# SODIMM_Connector.net
KiCad netlist of a schematic drawn in Altium Designer
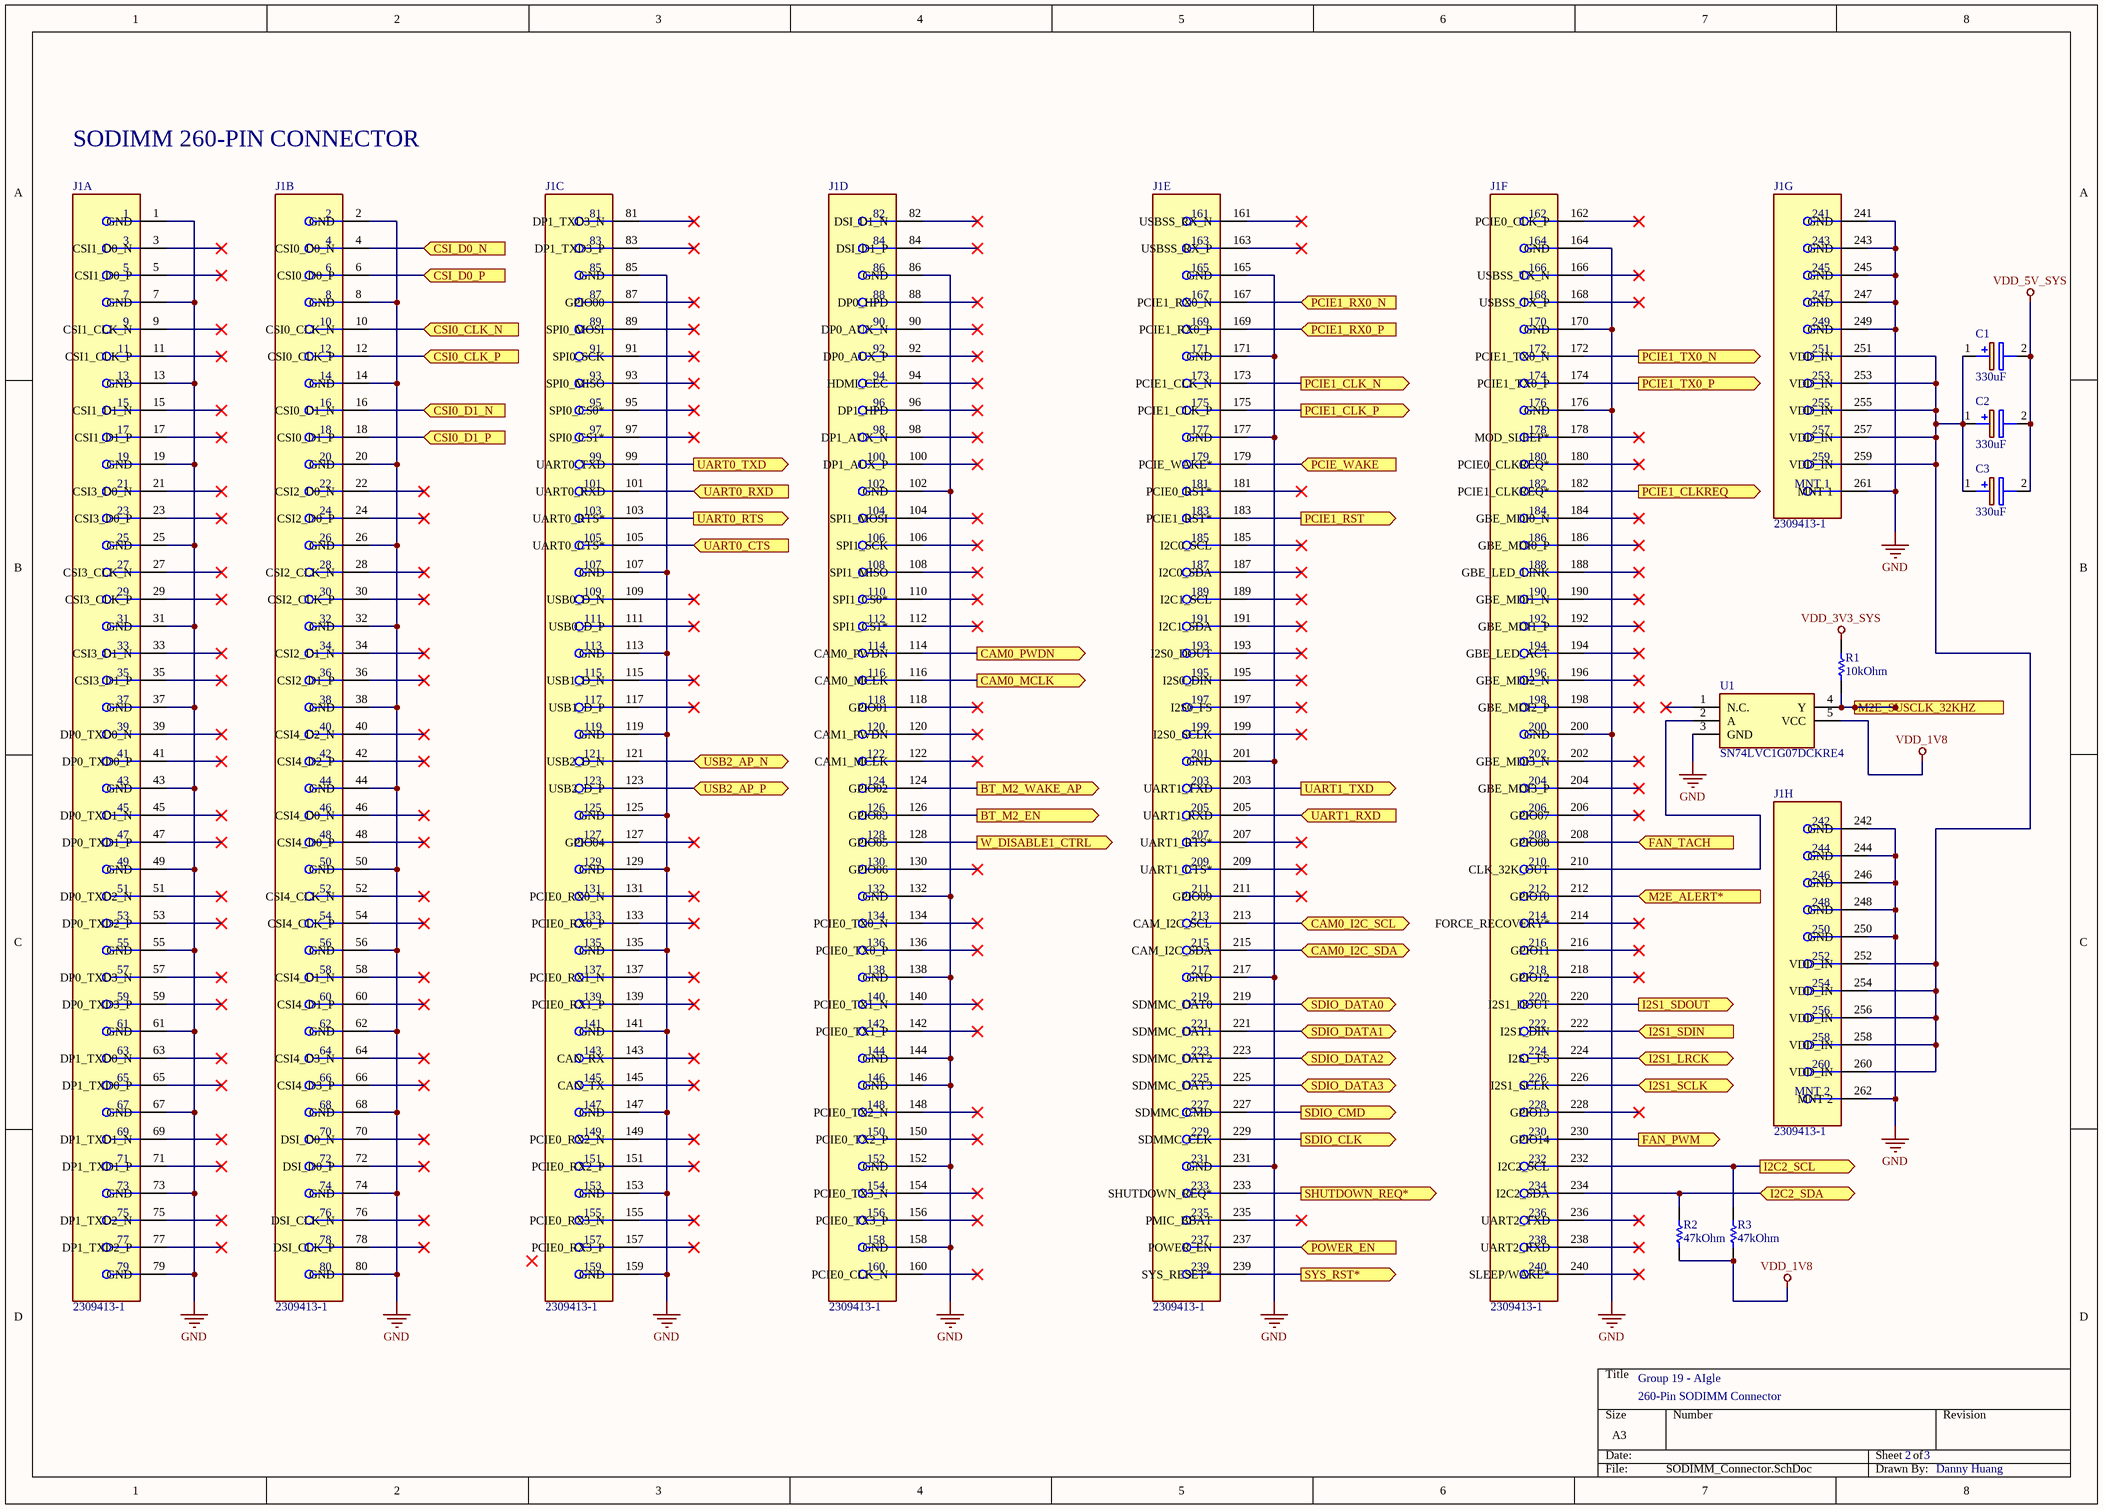
[diagram p0: SODIMM_Connector.SchDoc]

(export (version "E")
  (design (tool "Eeschema 10.0.6"))
  (components
    (comp (ref "C1")
      (value "330uF")
      (footprint "SamacSys:CAPPM3528X210N")
      (description "Capacitor Polarised")
      (fields
        (field (name "MANUFACTURER_PART_NUMBER") "T520B337M006ATE040")
        (field (name "MOUSER PART NUMBER") "80-T520B337M06ATE040")
      )
      (libsource (lib "*") (part "T520B337M006ATE040"))
    )
    (comp (ref "C2")
      (value "330uF")
      (footprint "SamacSys:CAPPM3528X210N")
      (description "Capacitor Polarised")
      (fields
        (field (name "MANUFACTURER_PART_NUMBER") "T520B337M006ATE040")
        (field (name "MOUSER PART NUMBER") "80-T520B337M06ATE040")
      )
      (libsource (lib "*") (part "T520B337M006ATE040"))
    )
    (comp (ref "C3")
      (value "330uF")
      (footprint "SamacSys:CAPPM3528X210N")
      (description "Capacitor Polarised")
      (fields
        (field (name "MANUFACTURER_PART_NUMBER") "T520B337M006ATE040")
        (field (name "MOUSER PART NUMBER") "80-T520B337M06ATE040")
      )
      (libsource (lib "*") (part "T520B337M006ATE040"))
    )
    (comp (ref "J1")
      (value "2309413-1")
      (footprint "FP-2309413-1-MFG")
      (description "DDR4 SODIMM 260P 9.2H STD")
      (fields
        (field (name "OCTOPART") "https://octopart.com/2309413-1-te+connectivity-84799194")
        (field (name "MANUFACTURER") "TE Connectivity")
      )
      (libsource (lib "Altium Content Vault") (part "4d1075b24ee2591bdcd47d674b3d2aa"))
    )
    (comp (ref "R1")
      (value "10kOhm")
      (footprint "RESC1005X40X25NL05T05")
      (fields (field (name "MANUFACTURER") "Vishay Dale") (field (name "PART NUMBER") "CRCW040210K0JNED"))
      (libsource (lib "Altium Content Vault") (part "RES"))
    )
    (comp (ref "R2")
      (value "47kOhm")
      (footprint "RESC1005X40X25LL05T05")
      (fields (field (name "MANUFACTURER") "Vishay Dale") (field (name "PART NUMBER") "CRCW040247K0JNED"))
      (libsource (lib "Altium Content Vault") (part "RES"))
    )
    (comp (ref "R3")
      (value "47kOhm")
      (footprint "RESC1005X40X25LL05T05")
      (fields (field (name "MANUFACTURER") "Vishay Dale") (field (name "PART NUMBER") "CRCW040247K0JNED"))
      (libsource (lib "Altium Content Vault") (part "RES"))
    )
    (comp (ref "U1")
      (value "SN74LVC1G07DCKRE4")
      (footprint "SamacSys:SOT65P210X110-5N")
      (description "Integrated Circuit")
      (fields (field (name "MOUSER PART NUMBER") "595-SN74LVC1G07DCKE4"))
      (libsource (lib "*") (part "SN74LVC1G07DCKRE4"))
    )
  )
  (nets
    (net (code "1") (name "/BT_M2_EN") (class "Default")
      (node (ref "J1") (pin "126") (pinfunction "126_126") (pintype "passive"))
    )
    (net (code "2") (name "/BT_M2_WAKE_AP") (class "Default")
      (node (ref "J1") (pin "124") (pinfunction "124_124") (pintype "passive"))
    )
    (net (code "3") (name "/CAM0_I2C_SCL") (class "Default")
      (node (ref "J1") (pin "213") (pinfunction "CAM_I2C_SCL_213") (pintype "passive"))
    )
    (net (code "4") (name "/CAM0_I2C_SDA") (class "Default")
      (node (ref "J1") (pin "215") (pinfunction "CAM_I2C_SDA_215") (pintype "passive"))
    )
    (net (code "5") (name "/CAM0_MCLK") (class "Default")
      (node (ref "J1") (pin "116") (pinfunction "CAM0_MCLK_116") (pintype "passive"))
    )
    (net (code "6") (name "/CAM0_PWDN") (class "Default")
      (node (ref "J1") (pin "114") (pinfunction "CAM0_PWDN_114") (pintype "passive"))
    )
    (net (code "7") (name "/CSI0_CLK_N") (class "Default")
      (node (ref "J1") (pin "10") (pinfunction "10_10") (pintype "passive"))
    )
    (net (code "8") (name "/CSI0_CLK_P") (class "Default")
      (node (ref "J1") (pin "12") (pinfunction "12_12") (pintype "passive"))
    )
    (net (code "9") (name "/CSI0_D1_N") (class "Default")
      (node (ref "J1") (pin "16") (pinfunction "16_16") (pintype "passive"))
    )
    (net (code "10") (name "/CSI0_D1_P") (class "Default")
      (node (ref "J1") (pin "18") (pinfunction "18_18") (pintype "passive"))
    )
    (net (code "11") (name "/CSI_D0_N") (class "Default")
      (node (ref "J1") (pin "4") (pinfunction "4_4") (pintype "passive"))
    )
    (net (code "12") (name "/CSI_D0_P") (class "Default")
      (node (ref "J1") (pin "6") (pinfunction "6_6") (pintype "passive"))
    )
    (net (code "13") (name "/FAN_PWM") (class "Default")
      (node (ref "J1") (pin "230") (pinfunction "230_230") (pintype "passive"))
    )
    (net (code "14") (name "/FAN_TACH") (class "Default")
      (node (ref "J1") (pin "208") (pinfunction "208_208") (pintype "passive"))
    )
    (net (code "15") (name "/I2C2_SCL") (class "Default")
      (node (ref "J1") (pin "232") (pinfunction "232_232") (pintype "passive"))
      (node (ref "R3") (pin "2") (pinfunction "2_2") (pintype "passive"))
    )
    (net (code "16") (name "/I2C2_SDA") (class "Default")
      (node (ref "J1") (pin "234") (pinfunction "234_234") (pintype "passive"))
      (node (ref "R2") (pin "2") (pinfunction "2_2") (pintype "passive"))
    )
    (net (code "17") (name "/I2S1_LRCK") (class "Default")
      (node (ref "J1") (pin "224") (pinfunction "224_224") (pintype "passive"))
    )
    (net (code "18") (name "/I2S1_SCLK") (class "Default")
      (node (ref "J1") (pin "226") (pinfunction "226_226") (pintype "passive"))
    )
    (net (code "19") (name "/I2S1_SDIN") (class "Default")
      (node (ref "J1") (pin "222") (pinfunction "222_222") (pintype "passive"))
    )
    (net (code "20") (name "/I2S1_SDOUT") (class "Default")
      (node (ref "J1") (pin "220") (pinfunction "220_220") (pintype "passive"))
    )
    (net (code "21") (name "/M2E_ALERT*") (class "Default")
      (node (ref "J1") (pin "212") (pinfunction "212_212") (pintype "passive"))
    )
    (net (code "22") (name "/M2E_SUSCLK_32KHZ") (class "Default")
      (node (ref "R1") (pin "1") (pinfunction "1_1") (pintype "passive"))
      (node (ref "U1") (pin "4") (pinfunction "Y_4") (pintype "passive"))
    )
    (net (code "23") (name "/PCIE1_CLKREQ") (class "Default")
      (node (ref "J1") (pin "182") (pinfunction "182_182") (pintype "passive"))
    )
    (net (code "24") (name "/PCIE1_CLK_N") (class "Default")
      (node (ref "J1") (pin "173") (pinfunction "173_173") (pintype "passive"))
    )
    (net (code "25") (name "/PCIE1_CLK_P") (class "Default")
      (node (ref "J1") (pin "175") (pinfunction "175_175") (pintype "passive"))
    )
    (net (code "26") (name "/PCIE1_RST") (class "Default")
      (node (ref "J1") (pin "183") (pinfunction "183_183") (pintype "passive"))
    )
    (net (code "27") (name "/PCIE1_RX0_N") (class "Default")
      (node (ref "J1") (pin "167") (pinfunction "167_167") (pintype "passive"))
    )
    (net (code "28") (name "/PCIE1_RX0_P") (class "Default")
      (node (ref "J1") (pin "169") (pinfunction "169_169") (pintype "passive"))
    )
    (net (code "29") (name "/PCIE1_TX0_N") (class "Default")
      (node (ref "J1") (pin "172") (pinfunction "172_172") (pintype "passive"))
    )
    (net (code "30") (name "/PCIE1_TX0_P") (class "Default")
      (node (ref "J1") (pin "174") (pinfunction "174_174") (pintype "passive"))
    )
    (net (code "31") (name "/PCIE_WAKE") (class "Default")
      (node (ref "J1") (pin "179") (pinfunction "179_179") (pintype "passive"))
    )
    (net (code "32") (name "/POWER_EN") (class "Default")
      (node (ref "J1") (pin "237") (pinfunction "237_237") (pintype "passive"))
    )
    (net (code "33") (name "/SDIO_CLK") (class "Default")
      (node (ref "J1") (pin "229") (pinfunction "229_229") (pintype "passive"))
    )
    (net (code "34") (name "/SDIO_CMD") (class "Default")
      (node (ref "J1") (pin "227") (pinfunction "227_227") (pintype "passive"))
    )
    (net (code "35") (name "/SDIO_DATA0") (class "Default")
      (node (ref "J1") (pin "219") (pinfunction "219_219") (pintype "passive"))
    )
    (net (code "36") (name "/SDIO_DATA1") (class "Default")
      (node (ref "J1") (pin "221") (pinfunction "221_221") (pintype "passive"))
    )
    (net (code "37") (name "/SDIO_DATA2") (class "Default")
      (node (ref "J1") (pin "223") (pinfunction "223_223") (pintype "passive"))
    )
    (net (code "38") (name "/SDIO_DATA3") (class "Default")
      (node (ref "J1") (pin "225") (pinfunction "225_225") (pintype "passive"))
    )
    (net (code "39") (name "/SHUTDOWN_REQ*") (class "Default")
      (node (ref "J1") (pin "233") (pinfunction "233_233") (pintype "passive"))
    )
    (net (code "40") (name "/SYS_RST*") (class "Default")
      (node (ref "J1") (pin "239") (pinfunction "239_239") (pintype "passive"))
    )
    (net (code "41") (name "/UART0_CTS") (class "Default")
      (node (ref "J1") (pin "105") (pinfunction "105_105") (pintype "passive"))
    )
    (net (code "42") (name "/UART0_RTS") (class "Default")
      (node (ref "J1") (pin "103") (pinfunction "103_103") (pintype "passive"))
    )
    (net (code "43") (name "/UART0_RXD") (class "Default")
      (node (ref "J1") (pin "101") (pinfunction "101_101") (pintype "passive"))
    )
    (net (code "44") (name "/UART0_TXD") (class "Default")
      (node (ref "J1") (pin "99") (pinfunction "99_99") (pintype "passive"))
    )
    (net (code "45") (name "/UART1_RXD") (class "Default")
      (node (ref "J1") (pin "205") (pinfunction "205_205") (pintype "passive"))
    )
    (net (code "46") (name "/UART1_TXD") (class "Default")
      (node (ref "J1") (pin "203") (pinfunction "203_203") (pintype "passive"))
    )
    (net (code "47") (name "/USB2_AP_N") (class "Default")
      (node (ref "J1") (pin "121") (pinfunction "121_121") (pintype "passive"))
    )
    (net (code "48") (name "/USB2_AP_P") (class "Default")
      (node (ref "J1") (pin "123") (pinfunction "123_123") (pintype "passive"))
    )
    (net (code "49") (name "/W_DISABLE1_CTRL") (class "Default")
      (node (ref "J1") (pin "128") (pinfunction "128_128") (pintype "passive"))
    )
    (net (code "50") (name "GND") (class "Default")
      (node (ref "J1") (pin "1") (pinfunction "GND_1") (pintype "passive"))
      (node (ref "J1") (pin "102") (pinfunction "102_102") (pintype "passive"))
      (node (ref "J1") (pin "107") (pinfunction "107_107") (pintype "passive"))
      (node (ref "J1") (pin "113") (pinfunction "113_113") (pintype "passive"))
      (node (ref "J1") (pin "119") (pinfunction "119_119") (pintype "passive"))
      (node (ref "J1") (pin "125") (pinfunction "125_125") (pintype "passive"))
      (node (ref "J1") (pin "129") (pinfunction "129_129") (pintype "passive"))
      (node (ref "J1") (pin "13") (pinfunction "GND_13") (pintype "passive"))
      (node (ref "J1") (pin "132") (pinfunction "132_132") (pintype "passive"))
      (node (ref "J1") (pin "135") (pinfunction "135_135") (pintype "passive"))
      (node (ref "J1") (pin "138") (pinfunction "138_138") (pintype "passive"))
      (node (ref "J1") (pin "14") (pinfunction "14_14") (pintype "passive"))
      (node (ref "J1") (pin "141") (pinfunction "141_141") (pintype "passive"))
      (node (ref "J1") (pin "144") (pinfunction "144_144") (pintype "passive"))
      (node (ref "J1") (pin "146") (pinfunction "146_146") (pintype "passive"))
      (node (ref "J1") (pin "147") (pinfunction "147_147") (pintype "passive"))
      (node (ref "J1") (pin "152") (pinfunction "152_152") (pintype "passive"))
      (node (ref "J1") (pin "153") (pinfunction "153_153") (pintype "passive"))
      (node (ref "J1") (pin "158") (pinfunction "158_158") (pintype "passive"))
      (node (ref "J1") (pin "159") (pinfunction "159_159") (pintype "passive"))
      (node (ref "J1") (pin "164") (pinfunction "164_164") (pintype "passive"))
      (node (ref "J1") (pin "165") (pinfunction "165_165") (pintype "passive"))
      (node (ref "J1") (pin "170") (pinfunction "170_170") (pintype "passive"))
      (node (ref "J1") (pin "171") (pinfunction "171_171") (pintype "passive"))
      (node (ref "J1") (pin "176") (pinfunction "176_176") (pintype "passive"))
      (node (ref "J1") (pin "177") (pinfunction "177_177") (pintype "passive"))
      (node (ref "J1") (pin "19") (pinfunction "GND_19") (pintype "passive"))
      (node (ref "J1") (pin "2") (pinfunction "2_2") (pintype "passive"))
      (node (ref "J1") (pin "20") (pinfunction "20_20") (pintype "passive"))
      (node (ref "J1") (pin "200") (pinfunction "200_200") (pintype "passive"))
      (node (ref "J1") (pin "201") (pinfunction "201_201") (pintype "passive"))
      (node (ref "J1") (pin "217") (pinfunction "217_217") (pintype "passive"))
      (node (ref "J1") (pin "231") (pinfunction "231_231") (pintype "passive"))
      (node (ref "J1") (pin "241") (pinfunction "241_241") (pintype "passive"))
      (node (ref "J1") (pin "242") (pinfunction "242_242") (pintype "passive"))
      (node (ref "J1") (pin "243") (pinfunction "243_243") (pintype "passive"))
      (node (ref "J1") (pin "244") (pinfunction "244_244") (pintype "passive"))
      (node (ref "J1") (pin "245") (pinfunction "245_245") (pintype "passive"))
      (node (ref "J1") (pin "246") (pinfunction "246_246") (pintype "passive"))
      (node (ref "J1") (pin "247") (pinfunction "247_247") (pintype "passive"))
      (node (ref "J1") (pin "248") (pinfunction "248_248") (pintype "passive"))
      (node (ref "J1") (pin "249") (pinfunction "249_249") (pintype "passive"))
      (node (ref "J1") (pin "25") (pinfunction "GND_25") (pintype "passive"))
      (node (ref "J1") (pin "250") (pinfunction "250_250") (pintype "passive"))
      (node (ref "J1") (pin "26") (pinfunction "26_26") (pintype "passive"))
      (node (ref "J1") (pin "261") (pinfunction "MNT_1_261") (pintype "passive"))
      (node (ref "J1") (pin "262") (pinfunction "MNT_2_262") (pintype "passive"))
      (node (ref "J1") (pin "31") (pinfunction "GND_31") (pintype "passive"))
      (node (ref "J1") (pin "32") (pinfunction "32_32") (pintype "passive"))
      (node (ref "J1") (pin "37") (pinfunction "GND_37") (pintype "passive"))
      (node (ref "J1") (pin "38") (pinfunction "38_38") (pintype "passive"))
      (node (ref "J1") (pin "43") (pinfunction "GND_43") (pintype "passive"))
      (node (ref "J1") (pin "44") (pinfunction "44_44") (pintype "passive"))
      (node (ref "J1") (pin "49") (pinfunction "GND_49") (pintype "passive"))
      (node (ref "J1") (pin "50") (pinfunction "50_50") (pintype "passive"))
      (node (ref "J1") (pin "55") (pinfunction "GND_55") (pintype "passive"))
      (node (ref "J1") (pin "56") (pinfunction "56_56") (pintype "passive"))
      (node (ref "J1") (pin "61") (pinfunction "GND_61") (pintype "passive"))
      (node (ref "J1") (pin "62") (pinfunction "62_62") (pintype "passive"))
      (node (ref "J1") (pin "67") (pinfunction "GND_67") (pintype "passive"))
      (node (ref "J1") (pin "68") (pinfunction "68_68") (pintype "passive"))
      (node (ref "J1") (pin "7") (pinfunction "GND_7") (pintype "passive"))
      (node (ref "J1") (pin "73") (pinfunction "GND_73") (pintype "passive"))
      (node (ref "J1") (pin "74") (pinfunction "74_74") (pintype "passive"))
      (node (ref "J1") (pin "79") (pinfunction "GND_79") (pintype "passive"))
      (node (ref "J1") (pin "8") (pinfunction "8_8") (pintype "passive"))
      (node (ref "J1") (pin "80") (pinfunction "80_80") (pintype "passive"))
      (node (ref "J1") (pin "85") (pinfunction "85_85") (pintype "passive"))
      (node (ref "J1") (pin "86") (pinfunction "86_86") (pintype "passive"))
      (node (ref "U1") (pin "3") (pinfunction "GND_3") (pintype "passive"))
    )
    (net (code "51") (name "Net-(C1-+)") (class "Default")
      (node (ref "C1") (pin "1") (pinfunction "+_1") (pintype "passive"))
      (node (ref "C2") (pin "1") (pinfunction "+_1") (pintype "passive"))
      (node (ref "C3") (pin "1") (pinfunction "+_1") (pintype "passive"))
      (node (ref "J1") (pin "251") (pinfunction "251_251") (pintype "passive"))
      (node (ref "J1") (pin "252") (pinfunction "252_252") (pintype "passive"))
      (node (ref "J1") (pin "253") (pinfunction "253_253") (pintype "passive"))
      (node (ref "J1") (pin "254") (pinfunction "254_254") (pintype "passive"))
      (node (ref "J1") (pin "255") (pinfunction "255_255") (pintype "passive"))
      (node (ref "J1") (pin "256") (pinfunction "256_256") (pintype "passive"))
      (node (ref "J1") (pin "257") (pinfunction "257_257") (pintype "passive"))
      (node (ref "J1") (pin "258") (pinfunction "258_258") (pintype "passive"))
      (node (ref "J1") (pin "259") (pinfunction "259_259") (pintype "passive"))
      (node (ref "J1") (pin "260") (pinfunction "260_260") (pintype "passive"))
    )
    (net (code "52") (name "Net-(U1-A)") (class "Default")
      (node (ref "J1") (pin "210") (pinfunction "210_210") (pintype "passive"))
      (node (ref "U1") (pin "2") (pinfunction "A_2") (pintype "passive"))
    )
    (net (code "53") (name "VDD_1V8") (class "Default")
      (node (ref "R2") (pin "1") (pinfunction "1_1") (pintype "passive"))
      (node (ref "R3") (pin "1") (pinfunction "1_1") (pintype "passive"))
      (node (ref "U1") (pin "5") (pinfunction "VCC_5") (pintype "passive"))
    )
    (net (code "54") (name "VDD_3V3_SYS") (class "Default")
      (node (ref "R1") (pin "2") (pinfunction "2_2") (pintype "passive"))
    )
    (net (code "55") (name "VDD_5V_SYS") (class "Default")
      (node (ref "C1") (pin "2") (pinfunction "-_2") (pintype "passive"))
      (node (ref "C2") (pin "2") (pinfunction "-_2") (pintype "passive"))
      (node (ref "C3") (pin "2") (pinfunction "-_2") (pintype "passive"))
    )
    (net (code "56") (name "unconnected-(J1-Pad22)") (class "Default")
      (node (ref "J1") (pin "22") (pinfunction "22_22") (pintype "passive+no_connect"))
    )
    (net (code "57") (name "unconnected-(J1-Pad24)") (class "Default")
      (node (ref "J1") (pin "24") (pinfunction "24_24") (pintype "passive+no_connect"))
    )
    (net (code "58") (name "unconnected-(J1-Pad28)") (class "Default")
      (node (ref "J1") (pin "28") (pinfunction "28_28") (pintype "passive+no_connect"))
    )
    (net (code "59") (name "unconnected-(J1-Pad30)") (class "Default")
      (node (ref "J1") (pin "30") (pinfunction "30_30") (pintype "passive+no_connect"))
    )
    (net (code "60") (name "unconnected-(J1-Pad34)") (class "Default")
      (node (ref "J1") (pin "34") (pinfunction "34_34") (pintype "passive+no_connect"))
    )
    (net (code "61") (name "unconnected-(J1-Pad36)") (class "Default")
      (node (ref "J1") (pin "36") (pinfunction "36_36") (pintype "passive+no_connect"))
    )
    (net (code "62") (name "unconnected-(J1-Pad40)") (class "Default")
      (node (ref "J1") (pin "40") (pinfunction "40_40") (pintype "passive+no_connect"))
    )
    (net (code "63") (name "unconnected-(J1-Pad42)") (class "Default")
      (node (ref "J1") (pin "42") (pinfunction "42_42") (pintype "passive+no_connect"))
    )
    (net (code "64") (name "unconnected-(J1-Pad46)") (class "Default")
      (node (ref "J1") (pin "46") (pinfunction "46_46") (pintype "passive+no_connect"))
    )
    (net (code "65") (name "unconnected-(J1-Pad48)") (class "Default")
      (node (ref "J1") (pin "48") (pinfunction "48_48") (pintype "passive+no_connect"))
    )
    (net (code "66") (name "unconnected-(J1-Pad52)") (class "Default")
      (node (ref "J1") (pin "52") (pinfunction "52_52") (pintype "passive+no_connect"))
    )
    (net (code "67") (name "unconnected-(J1-Pad54)") (class "Default")
      (node (ref "J1") (pin "54") (pinfunction "54_54") (pintype "passive+no_connect"))
    )
    (net (code "68") (name "unconnected-(J1-Pad58)") (class "Default")
      (node (ref "J1") (pin "58") (pinfunction "58_58") (pintype "passive+no_connect"))
    )
    (net (code "69") (name "unconnected-(J1-Pad60)") (class "Default")
      (node (ref "J1") (pin "60") (pinfunction "60_60") (pintype "passive+no_connect"))
    )
    (net (code "70") (name "unconnected-(J1-Pad64)") (class "Default")
      (node (ref "J1") (pin "64") (pinfunction "64_64") (pintype "passive+no_connect"))
    )
    (net (code "71") (name "unconnected-(J1-Pad66)") (class "Default")
      (node (ref "J1") (pin "66") (pinfunction "66_66") (pintype "passive+no_connect"))
    )
    (net (code "72") (name "unconnected-(J1-Pad70)") (class "Default")
      (node (ref "J1") (pin "70") (pinfunction "70_70") (pintype "passive+no_connect"))
    )
    (net (code "73") (name "unconnected-(J1-Pad72)") (class "Default")
      (node (ref "J1") (pin "72") (pinfunction "72_72") (pintype "passive+no_connect"))
    )
    (net (code "74") (name "unconnected-(J1-Pad76)") (class "Default")
      (node (ref "J1") (pin "76") (pinfunction "76_76") (pintype "passive+no_connect"))
    )
    (net (code "75") (name "unconnected-(J1-Pad78)") (class "Default")
      (node (ref "J1") (pin "78") (pinfunction "78_78") (pintype "passive+no_connect"))
    )
    (net (code "76") (name "unconnected-(J1-Pad81)") (class "Default")
      (node (ref "J1") (pin "81") (pinfunction "81_81") (pintype "passive+no_connect"))
    )
    (net (code "77") (name "unconnected-(J1-Pad82)") (class "Default")
      (node (ref "J1") (pin "82") (pinfunction "82_82") (pintype "passive+no_connect"))
    )
    (net (code "78") (name "unconnected-(J1-Pad83)") (class "Default")
      (node (ref "J1") (pin "83") (pinfunction "83_83") (pintype "passive+no_connect"))
    )
    (net (code "79") (name "unconnected-(J1-Pad84)") (class "Default")
      (node (ref "J1") (pin "84") (pinfunction "84_84") (pintype "passive+no_connect"))
    )
    (net (code "80") (name "unconnected-(J1-Pad87)") (class "Default")
      (node (ref "J1") (pin "87") (pinfunction "87_87") (pintype "passive+no_connect"))
    )
    (net (code "81") (name "unconnected-(J1-Pad88)") (class "Default")
      (node (ref "J1") (pin "88") (pinfunction "88_88") (pintype "passive+no_connect"))
    )
    (net (code "82") (name "unconnected-(J1-Pad89)") (class "Default")
      (node (ref "J1") (pin "89") (pinfunction "89_89") (pintype "passive+no_connect"))
    )
    (net (code "83") (name "unconnected-(J1-Pad90)") (class "Default")
      (node (ref "J1") (pin "90") (pinfunction "90_90") (pintype "passive+no_connect"))
    )
    (net (code "84") (name "unconnected-(J1-Pad91)") (class "Default")
      (node (ref "J1") (pin "91") (pinfunction "91_91") (pintype "passive+no_connect"))
    )
    (net (code "85") (name "unconnected-(J1-Pad92)") (class "Default")
      (node (ref "J1") (pin "92") (pinfunction "92_92") (pintype "passive+no_connect"))
    )
    (net (code "86") (name "unconnected-(J1-Pad93)") (class "Default")
      (node (ref "J1") (pin "93") (pinfunction "93_93") (pintype "passive+no_connect"))
    )
    (net (code "87") (name "unconnected-(J1-Pad94)") (class "Default")
      (node (ref "J1") (pin "94") (pinfunction "94_94") (pintype "passive+no_connect"))
    )
    (net (code "88") (name "unconnected-(J1-Pad95)") (class "Default")
      (node (ref "J1") (pin "95") (pinfunction "95_95") (pintype "passive+no_connect"))
    )
    (net (code "89") (name "unconnected-(J1-Pad96)") (class "Default")
      (node (ref "J1") (pin "96") (pinfunction "96_96") (pintype "passive+no_connect"))
    )
    (net (code "90") (name "unconnected-(J1-Pad97)") (class "Default")
      (node (ref "J1") (pin "97") (pinfunction "97_97") (pintype "passive+no_connect"))
    )
    (net (code "91") (name "unconnected-(J1-Pad98)") (class "Default")
      (node (ref "J1") (pin "98") (pinfunction "98_98") (pintype "passive+no_connect"))
    )
    (net (code "92") (name "unconnected-(J1-Pad100)") (class "Default")
      (node (ref "J1") (pin "100") (pinfunction "100_100") (pintype "passive+no_connect"))
    )
    (net (code "93") (name "unconnected-(J1-Pad104)") (class "Default")
      (node (ref "J1") (pin "104") (pinfunction "104_104") (pintype "passive+no_connect"))
    )
    (net (code "94") (name "unconnected-(J1-Pad106)") (class "Default")
      (node (ref "J1") (pin "106") (pinfunction "106_106") (pintype "passive+no_connect"))
    )
    (net (code "95") (name "unconnected-(J1-Pad108)") (class "Default")
      (node (ref "J1") (pin "108") (pinfunction "108_108") (pintype "passive+no_connect"))
    )
    (net (code "96") (name "unconnected-(J1-Pad109)") (class "Default")
      (node (ref "J1") (pin "109") (pinfunction "109_109") (pintype "passive+no_connect"))
    )
    (net (code "97") (name "unconnected-(J1-Pad110)") (class "Default")
      (node (ref "J1") (pin "110") (pinfunction "110_110") (pintype "passive+no_connect"))
    )
    (net (code "98") (name "unconnected-(J1-Pad111)") (class "Default")
      (node (ref "J1") (pin "111") (pinfunction "111_111") (pintype "passive+no_connect"))
    )
    (net (code "99") (name "unconnected-(J1-Pad112)") (class "Default")
      (node (ref "J1") (pin "112") (pinfunction "112_112") (pintype "passive+no_connect"))
    )
    (net (code "100") (name "unconnected-(J1-Pad115)") (class "Default")
      (node (ref "J1") (pin "115") (pinfunction "115_115") (pintype "passive+no_connect"))
    )
    (net (code "101") (name "unconnected-(J1-Pad117)") (class "Default")
      (node (ref "J1") (pin "117") (pinfunction "117_117") (pintype "passive+no_connect"))
    )
    (net (code "102") (name "unconnected-(J1-Pad118)") (class "Default")
      (node (ref "J1") (pin "118") (pinfunction "118_118") (pintype "passive+no_connect"))
    )
    (net (code "103") (name "unconnected-(J1-Pad120)") (class "Default")
      (node (ref "J1") (pin "120") (pinfunction "120_120") (pintype "passive+no_connect"))
    )
    (net (code "104") (name "unconnected-(J1-Pad122)") (class "Default")
      (node (ref "J1") (pin "122") (pinfunction "122_122") (pintype "passive+no_connect"))
    )
    (net (code "105") (name "unconnected-(J1-Pad127)") (class "Default")
      (node (ref "J1") (pin "127") (pinfunction "127_127") (pintype "passive+no_connect"))
    )
    (net (code "106") (name "unconnected-(J1-Pad130)") (class "Default")
      (node (ref "J1") (pin "130") (pinfunction "130_130") (pintype "passive+no_connect"))
    )
    (net (code "107") (name "unconnected-(J1-Pad131)") (class "Default")
      (node (ref "J1") (pin "131") (pinfunction "131_131") (pintype "passive+no_connect"))
    )
    (net (code "108") (name "unconnected-(J1-Pad133)") (class "Default")
      (node (ref "J1") (pin "133") (pinfunction "133_133") (pintype "passive+no_connect"))
    )
    (net (code "109") (name "unconnected-(J1-Pad134)") (class "Default")
      (node (ref "J1") (pin "134") (pinfunction "134_134") (pintype "passive+no_connect"))
    )
    (net (code "110") (name "unconnected-(J1-Pad136)") (class "Default")
      (node (ref "J1") (pin "136") (pinfunction "136_136") (pintype "passive+no_connect"))
    )
    (net (code "111") (name "unconnected-(J1-Pad137)") (class "Default")
      (node (ref "J1") (pin "137") (pinfunction "137_137") (pintype "passive+no_connect"))
    )
    (net (code "112") (name "unconnected-(J1-Pad139)") (class "Default")
      (node (ref "J1") (pin "139") (pinfunction "139_139") (pintype "passive+no_connect"))
    )
    (net (code "113") (name "unconnected-(J1-Pad140)") (class "Default")
      (node (ref "J1") (pin "140") (pinfunction "140_140") (pintype "passive+no_connect"))
    )
    (net (code "114") (name "unconnected-(J1-Pad142)") (class "Default")
      (node (ref "J1") (pin "142") (pinfunction "142_142") (pintype "passive+no_connect"))
    )
    (net (code "115") (name "unconnected-(J1-Pad143)") (class "Default")
      (node (ref "J1") (pin "143") (pinfunction "143_143") (pintype "passive+no_connect"))
    )
    (net (code "116") (name "unconnected-(J1-Pad145)") (class "Default")
      (node (ref "J1") (pin "145") (pinfunction "145_145") (pintype "passive+no_connect"))
    )
    (net (code "117") (name "unconnected-(J1-Pad148)") (class "Default")
      (node (ref "J1") (pin "148") (pinfunction "148_148") (pintype "passive+no_connect"))
    )
    (net (code "118") (name "unconnected-(J1-Pad149)") (class "Default")
      (node (ref "J1") (pin "149") (pinfunction "149_149") (pintype "passive+no_connect"))
    )
    (net (code "119") (name "unconnected-(J1-Pad150)") (class "Default")
      (node (ref "J1") (pin "150") (pinfunction "150_150") (pintype "passive+no_connect"))
    )
    (net (code "120") (name "unconnected-(J1-Pad151)") (class "Default")
      (node (ref "J1") (pin "151") (pinfunction "151_151") (pintype "passive+no_connect"))
    )
    (net (code "121") (name "unconnected-(J1-Pad154)") (class "Default")
      (node (ref "J1") (pin "154") (pinfunction "154_154") (pintype "passive+no_connect"))
    )
    (net (code "122") (name "unconnected-(J1-Pad155)") (class "Default")
      (node (ref "J1") (pin "155") (pinfunction "155_155") (pintype "passive+no_connect"))
    )
    (net (code "123") (name "unconnected-(J1-Pad156)") (class "Default")
      (node (ref "J1") (pin "156") (pinfunction "156_156") (pintype "passive+no_connect"))
    )
    (net (code "124") (name "unconnected-(J1-Pad157)") (class "Default")
      (node (ref "J1") (pin "157") (pinfunction "157_157") (pintype "passive+no_connect"))
    )
    (net (code "125") (name "unconnected-(J1-Pad160)") (class "Default")
      (node (ref "J1") (pin "160") (pinfunction "160_160") (pintype "passive+no_connect"))
    )
    (net (code "126") (name "unconnected-(J1-Pad161)") (class "Default")
      (node (ref "J1") (pin "161") (pinfunction "161_161") (pintype "passive+no_connect"))
    )
    (net (code "127") (name "unconnected-(J1-Pad162)") (class "Default")
      (node (ref "J1") (pin "162") (pinfunction "162_162") (pintype "passive+no_connect"))
    )
    (net (code "128") (name "unconnected-(J1-Pad163)") (class "Default")
      (node (ref "J1") (pin "163") (pinfunction "163_163") (pintype "passive+no_connect"))
    )
    (net (code "129") (name "unconnected-(J1-Pad166)") (class "Default")
      (node (ref "J1") (pin "166") (pinfunction "166_166") (pintype "passive+no_connect"))
    )
    (net (code "130") (name "unconnected-(J1-Pad168)") (class "Default")
      (node (ref "J1") (pin "168") (pinfunction "168_168") (pintype "passive+no_connect"))
    )
    (net (code "131") (name "unconnected-(J1-Pad178)") (class "Default")
      (node (ref "J1") (pin "178") (pinfunction "178_178") (pintype "passive+no_connect"))
    )
    (net (code "132") (name "unconnected-(J1-Pad180)") (class "Default")
      (node (ref "J1") (pin "180") (pinfunction "180_180") (pintype "passive+no_connect"))
    )
    (net (code "133") (name "unconnected-(J1-Pad181)") (class "Default")
      (node (ref "J1") (pin "181") (pinfunction "181_181") (pintype "passive+no_connect"))
    )
    (net (code "134") (name "unconnected-(J1-Pad184)") (class "Default")
      (node (ref "J1") (pin "184") (pinfunction "184_184") (pintype "passive+no_connect"))
    )
    (net (code "135") (name "unconnected-(J1-Pad185)") (class "Default")
      (node (ref "J1") (pin "185") (pinfunction "185_185") (pintype "passive+no_connect"))
    )
    (net (code "136") (name "unconnected-(J1-Pad186)") (class "Default")
      (node (ref "J1") (pin "186") (pinfunction "186_186") (pintype "passive+no_connect"))
    )
    (net (code "137") (name "unconnected-(J1-Pad187)") (class "Default")
      (node (ref "J1") (pin "187") (pinfunction "187_187") (pintype "passive+no_connect"))
    )
    (net (code "138") (name "unconnected-(J1-Pad188)") (class "Default")
      (node (ref "J1") (pin "188") (pinfunction "188_188") (pintype "passive+no_connect"))
    )
    (net (code "139") (name "unconnected-(J1-Pad189)") (class "Default")
      (node (ref "J1") (pin "189") (pinfunction "189_189") (pintype "passive+no_connect"))
    )
    (net (code "140") (name "unconnected-(J1-Pad190)") (class "Default")
      (node (ref "J1") (pin "190") (pinfunction "190_190") (pintype "passive+no_connect"))
    )
    (net (code "141") (name "unconnected-(J1-Pad191)") (class "Default")
      (node (ref "J1") (pin "191") (pinfunction "191_191") (pintype "passive+no_connect"))
    )
    (net (code "142") (name "unconnected-(J1-Pad192)") (class "Default")
      (node (ref "J1") (pin "192") (pinfunction "192_192") (pintype "passive+no_connect"))
    )
    (net (code "143") (name "unconnected-(J1-Pad193)") (class "Default")
      (node (ref "J1") (pin "193") (pinfunction "193_193") (pintype "passive+no_connect"))
    )
    (net (code "144") (name "unconnected-(J1-Pad194)") (class "Default")
      (node (ref "J1") (pin "194") (pinfunction "194_194") (pintype "passive+no_connect"))
    )
    (net (code "145") (name "unconnected-(J1-Pad195)") (class "Default")
      (node (ref "J1") (pin "195") (pinfunction "195_195") (pintype "passive+no_connect"))
    )
    (net (code "146") (name "unconnected-(J1-Pad196)") (class "Default")
      (node (ref "J1") (pin "196") (pinfunction "196_196") (pintype "passive+no_connect"))
    )
    (net (code "147") (name "unconnected-(J1-Pad197)") (class "Default")
      (node (ref "J1") (pin "197") (pinfunction "197_197") (pintype "passive+no_connect"))
    )
    (net (code "148") (name "unconnected-(J1-Pad198)") (class "Default")
      (node (ref "J1") (pin "198") (pinfunction "198_198") (pintype "passive+no_connect"))
    )
    (net (code "149") (name "unconnected-(J1-Pad199)") (class "Default")
      (node (ref "J1") (pin "199") (pinfunction "199_199") (pintype "passive+no_connect"))
    )
    (net (code "150") (name "unconnected-(J1-Pad202)") (class "Default")
      (node (ref "J1") (pin "202") (pinfunction "202_202") (pintype "passive+no_connect"))
    )
    (net (code "151") (name "unconnected-(J1-Pad204)") (class "Default")
      (node (ref "J1") (pin "204") (pinfunction "204_204") (pintype "passive+no_connect"))
    )
    (net (code "152") (name "unconnected-(J1-Pad206)") (class "Default")
      (node (ref "J1") (pin "206") (pinfunction "206_206") (pintype "passive+no_connect"))
    )
    (net (code "153") (name "unconnected-(J1-Pad207)") (class "Default")
      (node (ref "J1") (pin "207") (pinfunction "207_207") (pintype "passive+no_connect"))
    )
    (net (code "154") (name "unconnected-(J1-Pad209)") (class "Default")
      (node (ref "J1") (pin "209") (pinfunction "209_209") (pintype "passive+no_connect"))
    )
    (net (code "155") (name "unconnected-(J1-Pad211)") (class "Default")
      (node (ref "J1") (pin "211") (pinfunction "211_211") (pintype "passive+no_connect"))
    )
    (net (code "156") (name "unconnected-(J1-Pad214)") (class "Default")
      (node (ref "J1") (pin "214") (pinfunction "214_214") (pintype "passive+no_connect"))
    )
    (net (code "157") (name "unconnected-(J1-Pad216)") (class "Default")
      (node (ref "J1") (pin "216") (pinfunction "216_216") (pintype "passive+no_connect"))
    )
    (net (code "158") (name "unconnected-(J1-Pad218)") (class "Default")
      (node (ref "J1") (pin "218") (pinfunction "218_218") (pintype "passive+no_connect"))
    )
    (net (code "159") (name "unconnected-(J1-Pad228)") (class "Default")
      (node (ref "J1") (pin "228") (pinfunction "228_228") (pintype "passive+no_connect"))
    )
    (net (code "160") (name "unconnected-(J1-Pad235)") (class "Default")
      (node (ref "J1") (pin "235") (pinfunction "235_235") (pintype "passive+no_connect"))
    )
    (net (code "161") (name "unconnected-(J1-Pad236)") (class "Default")
      (node (ref "J1") (pin "236") (pinfunction "236_236") (pintype "passive+no_connect"))
    )
    (net (code "162") (name "unconnected-(J1-Pad238)") (class "Default")
      (node (ref "J1") (pin "238") (pinfunction "238_238") (pintype "passive+no_connect"))
    )
    (net (code "163") (name "unconnected-(J1-Pad240)") (class "Default")
      (node (ref "J1") (pin "240") (pinfunction "240_240") (pintype "passive+no_connect"))
    )
    (net (code "164") (name "unconnected-(J1A-CSI1_CLK_N-Pad9)") (class "Default")
      (node (ref "J1") (pin "9") (pinfunction "CSI1_CLK_N_9") (pintype "passive+no_connect"))
    )
    (net (code "165") (name "unconnected-(J1A-CSI1_CLK_P-Pad11)") (class "Default")
      (node (ref "J1") (pin "11") (pinfunction "CSI1_CLK_P_11") (pintype "passive+no_connect"))
    )
    (net (code "166") (name "unconnected-(J1A-CSI1_D0_N-Pad3)") (class "Default")
      (node (ref "J1") (pin "3") (pinfunction "CSI1_D0_N_3") (pintype "passive+no_connect"))
    )
    (net (code "167") (name "unconnected-(J1A-CSI1_D0_P-Pad5)") (class "Default")
      (node (ref "J1") (pin "5") (pinfunction "CSI1_D0_P_5") (pintype "passive+no_connect"))
    )
    (net (code "168") (name "unconnected-(J1A-CSI1_D1_N-Pad15)") (class "Default")
      (node (ref "J1") (pin "15") (pinfunction "CSI1_D1_N_15") (pintype "passive+no_connect"))
    )
    (net (code "169") (name "unconnected-(J1A-CSI1_D1_P-Pad17)") (class "Default")
      (node (ref "J1") (pin "17") (pinfunction "CSI1_D1_P_17") (pintype "passive+no_connect"))
    )
    (net (code "170") (name "unconnected-(J1A-CSI3_CLK_N-Pad27)") (class "Default")
      (node (ref "J1") (pin "27") (pinfunction "CSI3_CLK_N_27") (pintype "passive+no_connect"))
    )
    (net (code "171") (name "unconnected-(J1A-CSI3_CLK_P-Pad29)") (class "Default")
      (node (ref "J1") (pin "29") (pinfunction "CSI3_CLK_P_29") (pintype "passive+no_connect"))
    )
    (net (code "172") (name "unconnected-(J1A-CSI3_D0_N-Pad21)") (class "Default")
      (node (ref "J1") (pin "21") (pinfunction "CSI3_D0_N_21") (pintype "passive+no_connect"))
    )
    (net (code "173") (name "unconnected-(J1A-CSI3_D0_P-Pad23)") (class "Default")
      (node (ref "J1") (pin "23") (pinfunction "CSI3_D0_P_23") (pintype "passive+no_connect"))
    )
    (net (code "174") (name "unconnected-(J1A-CSI3_D1_N-Pad33)") (class "Default")
      (node (ref "J1") (pin "33") (pinfunction "CSI3_D1_N_33") (pintype "passive+no_connect"))
    )
    (net (code "175") (name "unconnected-(J1A-CSI3_D1_P-Pad35)") (class "Default")
      (node (ref "J1") (pin "35") (pinfunction "CSI3_D1_P_35") (pintype "passive+no_connect"))
    )
    (net (code "176") (name "unconnected-(J1A-DP0_TXD0_N-Pad39)") (class "Default")
      (node (ref "J1") (pin "39") (pinfunction "DP0_TXD0_N_39") (pintype "passive+no_connect"))
    )
    (net (code "177") (name "unconnected-(J1A-DP0_TXD0_P-Pad41)") (class "Default")
      (node (ref "J1") (pin "41") (pinfunction "DP0_TXD0_P_41") (pintype "passive+no_connect"))
    )
    (net (code "178") (name "unconnected-(J1A-DP0_TXD1_N-Pad45)") (class "Default")
      (node (ref "J1") (pin "45") (pinfunction "DP0_TXD1_N_45") (pintype "passive+no_connect"))
    )
    (net (code "179") (name "unconnected-(J1A-DP0_TXD1_P-Pad47)") (class "Default")
      (node (ref "J1") (pin "47") (pinfunction "DP0_TXD1_P_47") (pintype "passive+no_connect"))
    )
    (net (code "180") (name "unconnected-(J1A-DP0_TXD2_N-Pad51)") (class "Default")
      (node (ref "J1") (pin "51") (pinfunction "DP0_TXD2_N_51") (pintype "passive+no_connect"))
    )
    (net (code "181") (name "unconnected-(J1A-DP0_TXD2_P-Pad53)") (class "Default")
      (node (ref "J1") (pin "53") (pinfunction "DP0_TXD2_P_53") (pintype "passive+no_connect"))
    )
    (net (code "182") (name "unconnected-(J1A-DP0_TXD3_N-Pad57)") (class "Default")
      (node (ref "J1") (pin "57") (pinfunction "DP0_TXD3_N_57") (pintype "passive+no_connect"))
    )
    (net (code "183") (name "unconnected-(J1A-DP0_TXD3_P-Pad59)") (class "Default")
      (node (ref "J1") (pin "59") (pinfunction "DP0_TXD3_P_59") (pintype "passive+no_connect"))
    )
    (net (code "184") (name "unconnected-(J1A-DP1_TXD0_N-Pad63)") (class "Default")
      (node (ref "J1") (pin "63") (pinfunction "DP1_TXD0_N_63") (pintype "passive+no_connect"))
    )
    (net (code "185") (name "unconnected-(J1A-DP1_TXD0_P-Pad65)") (class "Default")
      (node (ref "J1") (pin "65") (pinfunction "DP1_TXD0_P_65") (pintype "passive+no_connect"))
    )
    (net (code "186") (name "unconnected-(J1A-DP1_TXD1_N-Pad69)") (class "Default")
      (node (ref "J1") (pin "69") (pinfunction "DP1_TXD1_N_69") (pintype "passive+no_connect"))
    )
    (net (code "187") (name "unconnected-(J1A-DP1_TXD1_P-Pad71)") (class "Default")
      (node (ref "J1") (pin "71") (pinfunction "DP1_TXD1_P_71") (pintype "passive+no_connect"))
    )
    (net (code "188") (name "unconnected-(J1A-DP1_TXD2_N-Pad75)") (class "Default")
      (node (ref "J1") (pin "75") (pinfunction "DP1_TXD2_N_75") (pintype "passive+no_connect"))
    )
    (net (code "189") (name "unconnected-(J1A-DP1_TXD2_P-Pad77)") (class "Default")
      (node (ref "J1") (pin "77") (pinfunction "DP1_TXD2_P_77") (pintype "passive+no_connect"))
    )
    (net (code "190") (name "unconnected-(U1-N.C.-Pad1)") (class "Default")
      (node (ref "U1") (pin "1") (pinfunction "N.C._1") (pintype "passive+no_connect"))
    )
  )
)
